# TouScruino-arm-ui2-v0.net
KiCad netlist of a schematic drawn in EAGLE
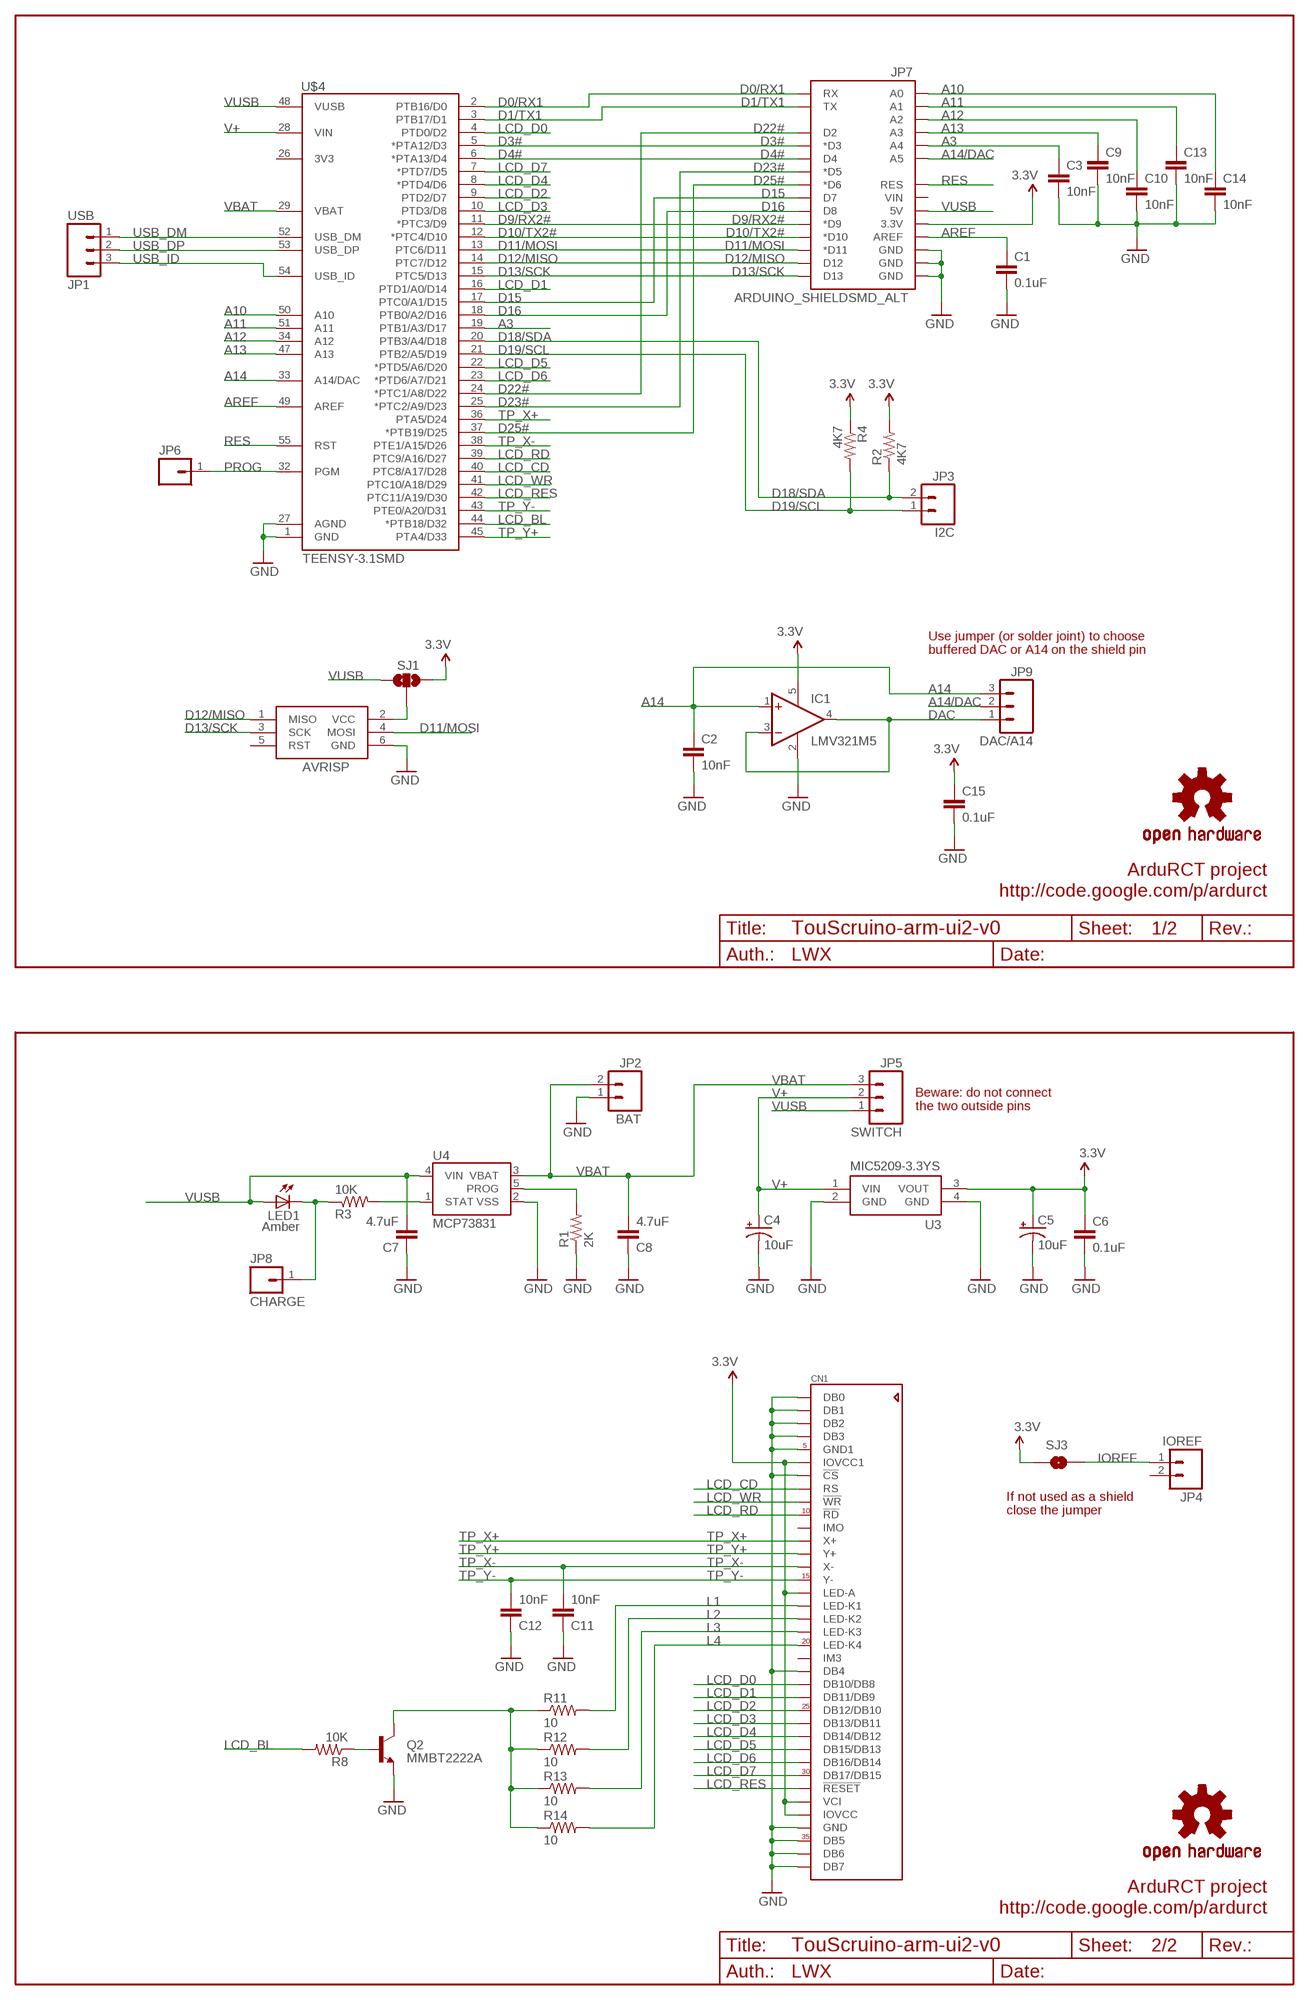
[diagram p0: schematic, sheet 1]

(export (version "E")
  (design (tool "Eeschema 10.0.6"))
  (components
    (comp (ref "AVRISP")
      (value "AVRISP")
      (footprint "eagle-import:2X3_SMD")
      (libsource (lib "eagle-import") (part "AVRISP"))
    )
    (comp (ref "C1")
      (value "0.1uF")
      (footprint "eagle-import:0805")
      (libsource (lib "eagle-import") (part "CAP0805"))
    )
    (comp (ref "C2")
      (value "10nF")
      (footprint "eagle-import:0805")
      (libsource (lib "eagle-import") (part "CAP0805"))
    )
    (comp (ref "C3")
      (value "10nF")
      (footprint "eagle-import:0805")
      (libsource (lib "eagle-import") (part "CAP0805"))
    )
    (comp (ref "C4")
      (value "10uF")
      (footprint "eagle-import:EIA3216")
      (libsource (lib "eagle-import") (part "CAP_POL1206"))
    )
    (comp (ref "C5")
      (value "10uF")
      (footprint "eagle-import:EIA3216")
      (libsource (lib "eagle-import") (part "CAP_POL1206"))
    )
    (comp (ref "C6")
      (value "0.1uF")
      (footprint "eagle-import:0805")
      (libsource (lib "eagle-import") (part "CAP0805"))
    )
    (comp (ref "C7")
      (value "4.7uF")
      (footprint "eagle-import:0805")
      (libsource (lib "eagle-import") (part "CAP0805"))
    )
    (comp (ref "C8")
      (value "4.7uF")
      (footprint "eagle-import:0805")
      (libsource (lib "eagle-import") (part "CAP0805"))
    )
    (comp (ref "C9")
      (value "10nF")
      (footprint "eagle-import:0805")
      (libsource (lib "eagle-import") (part "CAP0805"))
    )
    (comp (ref "C10")
      (value "10nF")
      (footprint "eagle-import:0805")
      (libsource (lib "eagle-import") (part "CAP0805"))
    )
    (comp (ref "C11")
      (value "10nF")
      (footprint "eagle-import:0805")
      (libsource (lib "eagle-import") (part "CAP0805"))
    )
    (comp (ref "C12")
      (value "10nF")
      (footprint "eagle-import:0805")
      (libsource (lib "eagle-import") (part "CAP0805"))
    )
    (comp (ref "C13")
      (value "10nF")
      (footprint "eagle-import:0805")
      (libsource (lib "eagle-import") (part "CAP0805"))
    )
    (comp (ref "C14")
      (value "10nF")
      (footprint "eagle-import:0805")
      (libsource (lib "eagle-import") (part "CAP0805"))
    )
    (comp (ref "C15")
      (value "0.1uF")
      (footprint "eagle-import:0805")
      (libsource (lib "eagle-import") (part "CAP0805"))
    )
    (comp (ref "CN1")
      (value "ILI9325_LCD1.0MM")
      (footprint "eagle-import:ILI9325_28INCH_TS")
      (libsource (lib "eagle-import") (part "ILI9325_LCD1.0MM"))
    )
    (comp (ref "IC1")
      (value "LMV321M5")
      (footprint "eagle-import:SOT23-5")
      (libsource (lib "eagle-import") (part "LMV321?M5"))
    )
    (comp (ref "JP1")
      (value "USB")
      (footprint "eagle-import:1X03_SMD_ALT")
      (libsource (lib "eagle-import") (part "M03SMD"))
    )
    (comp (ref "JP2")
      (value "BAT")
      (footprint "eagle-import:JST-2-SMD")
      (libsource (lib "eagle-import") (part "M02-JST-2MM-SMT"))
    )
    (comp (ref "JP3")
      (value "I2C")
      (footprint "eagle-import:1X02_SMD_ALT")
      (libsource (lib "eagle-import") (part "M02SMD_ALT"))
    )
    (comp (ref "JP4")
      (value "IOREF")
      (footprint "eagle-import:1X02_SMD_ALT")
      (libsource (lib "eagle-import") (part "M02SMD_ALT"))
    )
    (comp (ref "JP5")
      (value "SWITCH")
      (footprint "eagle-import:1X03_SMD_TH")
      (libsource (lib "eagle-import") (part "M03SMD_TH"))
    )
    (comp (ref "JP6")
      (value "M01SMD_TH")
      (footprint "eagle-import:1X01_SMD_TH")
      (libsource (lib "eagle-import") (part "M01SMD_TH"))
    )
    (comp (ref "JP7")
      (value "ARDUINO_SHIELDSMD_ALT")
      (footprint "eagle-import:ARDUINO_SHIELD_SMD_ALT")
      (libsource (lib "eagle-import") (part "ARDUINO_SHIELDSMD_ALT"))
    )
    (comp (ref "JP8")
      (value "CHARGE")
      (footprint "eagle-import:1X01_SMD")
      (libsource (lib "eagle-import") (part "M01SMD"))
    )
    (comp (ref "JP9")
      (value "DAC/A14")
      (footprint "eagle-import:1X03_SMD_SJ")
      (libsource (lib "eagle-import") (part "M03SMD_SJ"))
    )
    (comp (ref "LED1")
      (value "Amber")
      (footprint "eagle-import:LED")
      (libsource (lib "eagle-import") (part "LED"))
    )
    (comp (ref "Q2")
      (value "MMBT2222A")
      (footprint "eagle-import:SOT23-3")
      (libsource (lib "eagle-import") (part "TRANSISTOR_NPNSOT23-3"))
    )
    (comp (ref "R1")
      (value "2K")
      (footprint "eagle-import:0805")
      (libsource (lib "eagle-import") (part "RESISTOR0805-RES"))
    )
    (comp (ref "R2")
      (value "4K7")
      (footprint "eagle-import:0805")
      (libsource (lib "eagle-import") (part "RESISTOR0805-RES"))
    )
    (comp (ref "R3")
      (value "10K")
      (footprint "eagle-import:0805")
      (libsource (lib "eagle-import") (part "RESISTOR0805-RES"))
    )
    (comp (ref "R4")
      (value "4K7")
      (footprint "eagle-import:0805")
      (libsource (lib "eagle-import") (part "RESISTOR0805-RES"))
    )
    (comp (ref "R8")
      (value "10K")
      (footprint "eagle-import:0805")
      (libsource (lib "eagle-import") (part "RESISTOR0805-RES"))
    )
    (comp (ref "R11")
      (value "10")
      (footprint "eagle-import:0805")
      (libsource (lib "eagle-import") (part "RESISTOR0805-RES"))
    )
    (comp (ref "R12")
      (value "10")
      (footprint "eagle-import:0805")
      (libsource (lib "eagle-import") (part "RESISTOR0805-RES"))
    )
    (comp (ref "R13")
      (value "10")
      (footprint "eagle-import:0805")
      (libsource (lib "eagle-import") (part "RESISTOR0805-RES"))
    )
    (comp (ref "R14")
      (value "10")
      (footprint "eagle-import:0805")
      (libsource (lib "eagle-import") (part "RESISTOR0805-RES"))
    )
    (comp (ref "SJ1")
      (value "SJ_2WAYS")
      (footprint "eagle-import:SJ_2WAYS")
      (libsource (lib "eagle-import") (part "SJ_2WAYS"))
    )
    (comp (ref "SJ3")
      (value "SOLDERJUMPERNO")
      (footprint "eagle-import:SJ_2S-NO")
      (libsource (lib "eagle-import") (part "SOLDERJUMPERNO"))
    )
    (comp (ref "U$3")
      (value "OSHW-LOGOM")
      (footprint "eagle-import:OSHW-LOGO-M")
      (libsource (lib "eagle-import") (part "OSHW-LOGOM"))
    )
    (comp (ref "U$4")
      (value "TEENSY-3.1SMD")
      (footprint "eagle-import:TEENSY-3.1_HSMD")
      (libsource (lib "eagle-import") (part "TEENSY-3.1SMD"))
    )
    (comp (ref "U$5")
      (value "OSHW-LOGOM")
      (footprint "eagle-import:OSHW-LOGO-M")
      (libsource (lib "eagle-import") (part "OSHW-LOGOM"))
    )
    (comp (ref "U3")
      (value "MIC5209-3.3YS")
      (footprint "eagle-import:SOT223")
      (libsource (lib "eagle-import") (part "MIC5209"))
    )
    (comp (ref "U4")
      (value "MCP73831")
      (footprint "eagle-import:SOT23-5")
      (libsource (lib "eagle-import") (part "MCP73831"))
    )
  )
  (nets
    (net (code "1") (name "/A3") (class "Default")
      (node (ref "C3") (pin "1") (pinfunction "1_1") (pintype "passive"))
      (node (ref "JP7") (pin "A4") (pinfunction "A4_A4") (pintype "bidirectional"))
      (node (ref "U$4") (pin "19") (pinfunction "PTB1/A3/D17_19") (pintype "bidirectional"))
    )
    (net (code "2") (name "/A10") (class "Default")
      (node (ref "C14") (pin "1") (pinfunction "1_1") (pintype "passive"))
      (node (ref "JP7") (pin "A0") (pinfunction "A0_A0") (pintype "bidirectional"))
      (node (ref "U$4") (pin "50") (pinfunction "A10_50") (pintype "bidirectional"))
    )
    (net (code "3") (name "/A11") (class "Default")
      (node (ref "C13") (pin "1") (pinfunction "1_1") (pintype "passive"))
      (node (ref "JP7") (pin "A1") (pinfunction "A1_A1") (pintype "bidirectional"))
      (node (ref "U$4") (pin "51") (pinfunction "A11_51") (pintype "bidirectional"))
    )
    (net (code "4") (name "/A12") (class "Default")
      (node (ref "C10") (pin "1") (pinfunction "1_1") (pintype "passive"))
      (node (ref "JP7") (pin "A2") (pinfunction "A2_A2") (pintype "bidirectional"))
      (node (ref "U$4") (pin "34") (pinfunction "A12_34") (pintype "bidirectional"))
    )
    (net (code "5") (name "/A13") (class "Default")
      (node (ref "C9") (pin "1") (pinfunction "1_1") (pintype "passive"))
      (node (ref "JP7") (pin "A3") (pinfunction "A3_A3") (pintype "bidirectional"))
      (node (ref "U$4") (pin "47") (pinfunction "A13_47") (pintype "bidirectional"))
    )
    (net (code "6") (name "/A14") (class "Default")
      (node (ref "C2") (pin "1") (pinfunction "1_1") (pintype "passive"))
      (node (ref "IC1") (pin "1") (pinfunction "+IN_1") (pintype "input"))
      (node (ref "JP9") (pin "3") (pinfunction "3_3") (pintype "passive"))
      (node (ref "U$4") (pin "33") (pinfunction "A14/DAC_33") (pintype "bidirectional"))
    )
    (net (code "7") (name "/A14{slash}DAC") (class "Default")
      (node (ref "JP7") (pin "A5") (pinfunction "A5_A5") (pintype "bidirectional"))
      (node (ref "JP9") (pin "2") (pinfunction "2_2") (pintype "passive"))
    )
    (net (code "8") (name "/AREF") (class "Default")
      (node (ref "C1") (pin "1") (pinfunction "1_1") (pintype "passive"))
      (node (ref "JP7") (pin "AREF") (pinfunction "AREF_AREF") (pintype "bidirectional"))
      (node (ref "U$4") (pin "49") (pinfunction "AREF_49") (pintype "bidirectional"))
    )
    (net (code "9") (name "/D0{slash}RX1") (class "Default")
      (node (ref "JP7") (pin "RX") (pinfunction "RX_RX") (pintype "bidirectional"))
      (node (ref "U$4") (pin "2") (pinfunction "PTB16/D0_2") (pintype "bidirectional"))
    )
    (net (code "10") (name "/D1{slash}TX1") (class "Default")
      (node (ref "JP7") (pin "TX") (pinfunction "TX_TX") (pintype "bidirectional"))
      (node (ref "U$4") (pin "3") (pinfunction "PTB17/D1_3") (pintype "bidirectional"))
    )
    (net (code "11") (name "/D3#") (class "Default")
      (node (ref "JP7") (pin "D3") (pinfunction "*D3_D3") (pintype "bidirectional"))
      (node (ref "U$4") (pin "5") (pinfunction "*PTA12/D3_5") (pintype "bidirectional"))
    )
    (net (code "12") (name "/D4#") (class "Default")
      (node (ref "JP7") (pin "D4") (pinfunction "D4_D4") (pintype "bidirectional"))
      (node (ref "U$4") (pin "6") (pinfunction "*PTA13/D4_6") (pintype "bidirectional"))
    )
    (net (code "13") (name "/D9{slash}RX2#") (class "Default")
      (node (ref "JP7") (pin "D9") (pinfunction "*D9_D9") (pintype "bidirectional"))
      (node (ref "U$4") (pin "11") (pinfunction "*PTC3/D9_11") (pintype "bidirectional"))
    )
    (net (code "14") (name "/D10{slash}TX2#") (class "Default")
      (node (ref "JP7") (pin "D10") (pinfunction "*D10_D10") (pintype "bidirectional"))
      (node (ref "U$4") (pin "12") (pinfunction "*PTC4/D10_12") (pintype "bidirectional"))
    )
    (net (code "15") (name "/D11{slash}MOSI") (class "Default")
      (node (ref "AVRISP") (pin "4") (pinfunction "MOSI_4") (pintype "output"))
      (node (ref "JP7") (pin "D11") (pinfunction "*D11_D11") (pintype "bidirectional"))
      (node (ref "U$4") (pin "13") (pinfunction "PTC6/D11_13") (pintype "bidirectional"))
    )
    (net (code "16") (name "/D12{slash}MISO") (class "Default")
      (node (ref "AVRISP") (pin "1") (pinfunction "MISO_1") (pintype "input"))
      (node (ref "JP7") (pin "D12") (pinfunction "D12_D12") (pintype "bidirectional"))
      (node (ref "U$4") (pin "14") (pinfunction "PTC7/D12_14") (pintype "bidirectional"))
    )
    (net (code "17") (name "/D13{slash}SCK") (class "Default")
      (node (ref "AVRISP") (pin "3") (pinfunction "SCK_3") (pintype "output"))
      (node (ref "JP7") (pin "D13") (pinfunction "D13_D13") (pintype "bidirectional"))
      (node (ref "U$4") (pin "15") (pinfunction "PTC5/D13_15") (pintype "bidirectional"))
    )
    (net (code "18") (name "/D15") (class "Default")
      (node (ref "JP7") (pin "D7") (pinfunction "D7_D7") (pintype "bidirectional"))
      (node (ref "U$4") (pin "17") (pinfunction "PTC0/A1/D15_17") (pintype "bidirectional"))
    )
    (net (code "19") (name "/D16") (class "Default")
      (node (ref "JP7") (pin "D8") (pinfunction "D8_D8") (pintype "bidirectional"))
      (node (ref "U$4") (pin "18") (pinfunction "PTB0/A2/D16_18") (pintype "bidirectional"))
    )
    (net (code "20") (name "/D18{slash}SDA") (class "Default")
      (node (ref "JP3") (pin "2") (pinfunction "2_2") (pintype "passive"))
      (node (ref "R2") (pin "1") (pinfunction "1_1") (pintype "passive"))
      (node (ref "U$4") (pin "20") (pinfunction "PTB3/A4/D18_20") (pintype "bidirectional"))
    )
    (net (code "21") (name "/D19{slash}SCL") (class "Default")
      (node (ref "JP3") (pin "1") (pinfunction "1_1") (pintype "passive"))
      (node (ref "R4") (pin "2") (pinfunction "2_2") (pintype "passive"))
      (node (ref "U$4") (pin "21") (pinfunction "PTB2/A5/D19_21") (pintype "bidirectional"))
    )
    (net (code "22") (name "/D22#") (class "Default")
      (node (ref "JP7") (pin "D2") (pinfunction "D2_D2") (pintype "bidirectional"))
      (node (ref "U$4") (pin "24") (pinfunction "*PTC1/A8/D22_24") (pintype "bidirectional"))
    )
    (net (code "23") (name "/D23#") (class "Default")
      (node (ref "JP7") (pin "D5") (pinfunction "*D5_D5") (pintype "bidirectional"))
      (node (ref "U$4") (pin "25") (pinfunction "*PTC2/A9/D23_25") (pintype "bidirectional"))
    )
    (net (code "24") (name "/D25#") (class "Default")
      (node (ref "JP7") (pin "D6") (pinfunction "*D6_D6") (pintype "bidirectional"))
      (node (ref "U$4") (pin "37") (pinfunction "*PTB19/D25_37") (pintype "bidirectional"))
    )
    (net (code "25") (name "/DAC") (class "Default")
      (node (ref "IC1") (pin "3") (pinfunction "-IN_3") (pintype "input"))
      (node (ref "IC1") (pin "4") (pinfunction "OUT_4") (pintype "output"))
      (node (ref "JP9") (pin "1") (pinfunction "1_1") (pintype "passive"))
    )
    (net (code "26") (name "/IOREF") (class "Default")
      (node (ref "JP4") (pin "1") (pinfunction "1_1") (pintype "passive"))
      (node (ref "SJ3") (pin "2") (pinfunction "2_2") (pintype "passive"))
    )
    (net (code "27") (name "/L1") (class "Default")
      (node (ref "CN1") (pin "17") (pinfunction "LED-K1_17") (pintype "passive"))
      (node (ref "R11") (pin "2") (pinfunction "2_2") (pintype "passive"))
    )
    (net (code "28") (name "/L2") (class "Default")
      (node (ref "CN1") (pin "18") (pinfunction "LED-K2_18") (pintype "passive"))
      (node (ref "R12") (pin "2") (pinfunction "2_2") (pintype "passive"))
    )
    (net (code "29") (name "/L3") (class "Default")
      (node (ref "CN1") (pin "19") (pinfunction "LED-K3_19") (pintype "passive"))
      (node (ref "R13") (pin "2") (pinfunction "2_2") (pintype "passive"))
    )
    (net (code "30") (name "/L4") (class "Default")
      (node (ref "CN1") (pin "20") (pinfunction "LED-K4_20") (pintype "passive"))
      (node (ref "R14") (pin "2") (pinfunction "2_2") (pintype "passive"))
    )
    (net (code "31") (name "/LCD_BL") (class "Default")
      (node (ref "R8") (pin "2") (pinfunction "2_2") (pintype "passive"))
      (node (ref "U$4") (pin "44") (pinfunction "*PTB18/D32_44") (pintype "bidirectional"))
    )
    (net (code "32") (name "/LCD_CD") (class "Default")
      (node (ref "CN1") (pin "8") (pinfunction "RS_8") (pintype "passive"))
      (node (ref "U$4") (pin "40") (pinfunction "PTC8/A17/D28_40") (pintype "bidirectional"))
    )
    (net (code "33") (name "/LCD_D0") (class "Default")
      (node (ref "CN1") (pin "23") (pinfunction "DB10/DB8_23") (pintype "passive"))
      (node (ref "U$4") (pin "4") (pinfunction "PTD0/D2_4") (pintype "bidirectional"))
    )
    (net (code "34") (name "/LCD_D1") (class "Default")
      (node (ref "CN1") (pin "24") (pinfunction "DB11/DB9_24") (pintype "passive"))
      (node (ref "U$4") (pin "16") (pinfunction "PTD1/A0/D14_16") (pintype "bidirectional"))
    )
    (net (code "35") (name "/LCD_D2") (class "Default")
      (node (ref "CN1") (pin "25") (pinfunction "DB12/DB10_25") (pintype "passive"))
      (node (ref "U$4") (pin "9") (pinfunction "PTD2/D7_9") (pintype "bidirectional"))
    )
    (net (code "36") (name "/LCD_D3") (class "Default")
      (node (ref "CN1") (pin "26") (pinfunction "DB13/DB11_26") (pintype "passive"))
      (node (ref "U$4") (pin "10") (pinfunction "PTD3/D8_10") (pintype "bidirectional"))
    )
    (net (code "37") (name "/LCD_D4") (class "Default")
      (node (ref "CN1") (pin "27") (pinfunction "DB14/DB12_27") (pintype "passive"))
      (node (ref "U$4") (pin "8") (pinfunction "*PTD4/D6_8") (pintype "bidirectional"))
    )
    (net (code "38") (name "/LCD_D5") (class "Default")
      (node (ref "CN1") (pin "28") (pinfunction "DB15/DB13_28") (pintype "passive"))
      (node (ref "U$4") (pin "22") (pinfunction "*PTD5/A6/D20_22") (pintype "bidirectional"))
    )
    (net (code "39") (name "/LCD_D6") (class "Default")
      (node (ref "CN1") (pin "29") (pinfunction "DB16/DB14_29") (pintype "passive"))
      (node (ref "U$4") (pin "23") (pinfunction "*PTD6/A7/D21_23") (pintype "bidirectional"))
    )
    (net (code "40") (name "/LCD_D7") (class "Default")
      (node (ref "CN1") (pin "30") (pinfunction "DB17/DB15_30") (pintype "passive"))
      (node (ref "U$4") (pin "7") (pinfunction "*PTD7/D5_7") (pintype "bidirectional"))
    )
    (net (code "41") (name "/LCD_RD") (class "Default")
      (node (ref "CN1") (pin "10") (pinfunction "~{RD}_10") (pintype "passive"))
      (node (ref "U$4") (pin "39") (pinfunction "PTC9/A16/D27_39") (pintype "bidirectional"))
    )
    (net (code "42") (name "/LCD_RES") (class "Default")
      (node (ref "CN1") (pin "31") (pinfunction "~{RESET}_31") (pintype "passive"))
      (node (ref "U$4") (pin "42") (pinfunction "PTC11/A19/D30_42") (pintype "bidirectional"))
    )
    (net (code "43") (name "/LCD_WR") (class "Default")
      (node (ref "CN1") (pin "9") (pinfunction "~{WR}_9") (pintype "passive"))
      (node (ref "U$4") (pin "41") (pinfunction "PTC10/A18/D29_41") (pintype "bidirectional"))
    )
    (net (code "44") (name "/PROG") (class "Default")
      (node (ref "JP6") (pin "1") (pinfunction "1_1") (pintype "passive"))
      (node (ref "U$4") (pin "32") (pinfunction "PGM_32") (pintype "bidirectional"))
    )
    (net (code "45") (name "/RES") (class "Default")
      (node (ref "JP7") (pin "RES") (pinfunction "RES_RES") (pintype "bidirectional"))
      (node (ref "U$4") (pin "55") (pinfunction "RST_55") (pintype "bidirectional"))
    )
    (net (code "46") (name "/TP_X+") (class "Default")
      (node (ref "CN1") (pin "12") (pinfunction "X+_12") (pintype "passive"))
      (node (ref "U$4") (pin "36") (pinfunction "PTA5/D24_36") (pintype "bidirectional"))
    )
    (net (code "47") (name "/TP_X-") (class "Default")
      (node (ref "C11") (pin "2") (pinfunction "2_2") (pintype "passive"))
      (node (ref "CN1") (pin "14") (pinfunction "X-_14") (pintype "passive"))
      (node (ref "U$4") (pin "38") (pinfunction "PTE1/A15/D26_38") (pintype "bidirectional"))
    )
    (net (code "48") (name "/TP_Y+") (class "Default")
      (node (ref "CN1") (pin "13") (pinfunction "Y+_13") (pintype "passive"))
      (node (ref "U$4") (pin "45") (pinfunction "PTA4/D33_45") (pintype "bidirectional"))
    )
    (net (code "49") (name "/TP_Y-") (class "Default")
      (node (ref "C12") (pin "2") (pinfunction "2_2") (pintype "passive"))
      (node (ref "CN1") (pin "15") (pinfunction "Y-_15") (pintype "passive"))
      (node (ref "U$4") (pin "43") (pinfunction "PTE0/A20/D31_43") (pintype "bidirectional"))
    )
    (net (code "50") (name "/USB_DM") (class "Default")
      (node (ref "JP1") (pin "1") (pinfunction "1_1") (pintype "passive"))
      (node (ref "U$4") (pin "52") (pinfunction "USB_DM_52") (pintype "bidirectional"))
    )
    (net (code "51") (name "/USB_DP") (class "Default")
      (node (ref "JP1") (pin "2") (pinfunction "2_2") (pintype "passive"))
      (node (ref "U$4") (pin "53") (pinfunction "USB_DP_53") (pintype "bidirectional"))
    )
    (net (code "52") (name "/USB_ID") (class "Default")
      (node (ref "JP1") (pin "3") (pinfunction "3_3") (pintype "passive"))
      (node (ref "U$4") (pin "54") (pinfunction "USB_ID_54") (pintype "bidirectional"))
    )
    (net (code "53") (name "/V+") (class "Default")
      (node (ref "C4") (pin "A") (pinfunction "+_A") (pintype "passive"))
      (node (ref "JP5") (pin "2") (pinfunction "2_2") (pintype "passive"))
      (node (ref "U$4") (pin "28") (pinfunction "VIN_28") (pintype "bidirectional"))
      (node (ref "U3") (pin "1") (pinfunction "VIN_1") (pintype "bidirectional"))
    )
    (net (code "54") (name "/VBAT") (class "Default")
      (node (ref "C8") (pin "2") (pinfunction "2_2") (pintype "passive"))
      (node (ref "JP2") (pin "2") (pinfunction "2_2") (pintype "passive"))
      (node (ref "JP5") (pin "3") (pinfunction "3_3") (pintype "passive"))
      (node (ref "U$4") (pin "29") (pinfunction "VBAT_29") (pintype "bidirectional"))
      (node (ref "U4") (pin "3") (pinfunction "VBAT_3") (pintype "power_in"))
    )
    (net (code "55") (name "/VUSB") (class "Default")
      (node (ref "C7") (pin "2") (pinfunction "2_2") (pintype "passive"))
      (node (ref "JP5") (pin "1") (pinfunction "1_1") (pintype "passive"))
      (node (ref "JP7") (pin "5V") (pinfunction "5V_5V") (pintype "bidirectional"))
      (node (ref "LED1") (pin "A1") (pinfunction "A_A1") (pintype "passive"))
      (node (ref "SJ1") (pin "1") (pinfunction "1_1") (pintype "passive"))
      (node (ref "U$4") (pin "48") (pinfunction "VUSB_48") (pintype "bidirectional"))
      (node (ref "U4") (pin "4") (pinfunction "VIN_4") (pintype "power_in"))
    )
    (net (code "56") (name "3.3V") (class "Default")
      (node (ref "C15") (pin "1") (pinfunction "1_1") (pintype "passive"))
      (node (ref "C5") (pin "A") (pinfunction "+_A") (pintype "passive"))
      (node (ref "C6") (pin "1") (pinfunction "1_1") (pintype "passive"))
      (node (ref "CN1") (pin "16") (pinfunction "LED-A_16") (pintype "passive"))
      (node (ref "CN1") (pin "32") (pinfunction "VCI_32") (pintype "power_in"))
      (node (ref "CN1") (pin "33") (pinfunction "IOVCC_33") (pintype "power_in"))
      (node (ref "CN1") (pin "6") (pinfunction "IOVCC1_6") (pintype "power_in"))
      (node (ref "IC1") (pin "5") (pinfunction "V+_5") (pintype "power_in"))
      (node (ref "JP7") (pin "3.3V") (pinfunction "3.3V_3.3V") (pintype "bidirectional"))
      (node (ref "R2") (pin "2") (pinfunction "2_2") (pintype "passive"))
      (node (ref "R4") (pin "1") (pinfunction "1_1") (pintype "passive"))
      (node (ref "SJ1") (pin "3") (pinfunction "3_3") (pintype "passive"))
      (node (ref "SJ3") (pin "1") (pinfunction "1_1") (pintype "passive"))
      (node (ref "U3") (pin "3") (pinfunction "VOUT_3") (pintype "bidirectional"))
    )
    (net (code "57") (name "GND") (class "Default")
      (node (ref "AVRISP") (pin "6") (pinfunction "GND_6") (pintype "power_in"))
      (node (ref "C1") (pin "2") (pinfunction "2_2") (pintype "passive"))
      (node (ref "C10") (pin "2") (pinfunction "2_2") (pintype "passive"))
      (node (ref "C11") (pin "1") (pinfunction "1_1") (pintype "passive"))
      (node (ref "C12") (pin "1") (pinfunction "1_1") (pintype "passive"))
      (node (ref "C13") (pin "2") (pinfunction "2_2") (pintype "passive"))
      (node (ref "C14") (pin "2") (pinfunction "2_2") (pintype "passive"))
      (node (ref "C15") (pin "2") (pinfunction "2_2") (pintype "passive"))
      (node (ref "C2") (pin "2") (pinfunction "2_2") (pintype "passive"))
      (node (ref "C3") (pin "2") (pinfunction "2_2") (pintype "passive"))
      (node (ref "C4") (pin "C") (pinfunction "-_C") (pintype "passive"))
      (node (ref "C5") (pin "C") (pinfunction "-_C") (pintype "passive"))
      (node (ref "C6") (pin "2") (pinfunction "2_2") (pintype "passive"))
      (node (ref "C7") (pin "1") (pinfunction "1_1") (pintype "passive"))
      (node (ref "C8") (pin "1") (pinfunction "1_1") (pintype "passive"))
      (node (ref "C9") (pin "2") (pinfunction "2_2") (pintype "passive"))
      (node (ref "CN1") (pin "1") (pinfunction "DB0_1") (pintype "passive"))
      (node (ref "CN1") (pin "2") (pinfunction "DB1_2") (pintype "passive"))
      (node (ref "CN1") (pin "22") (pinfunction "DB4_22") (pintype "passive"))
      (node (ref "CN1") (pin "3") (pinfunction "DB2_3") (pintype "passive"))
      (node (ref "CN1") (pin "34") (pinfunction "GND_34") (pintype "power_in"))
      (node (ref "CN1") (pin "35") (pinfunction "DB5_35") (pintype "passive"))
      (node (ref "CN1") (pin "36") (pinfunction "DB6_36") (pintype "passive"))
      (node (ref "CN1") (pin "37") (pinfunction "DB7_37") (pintype "passive"))
      (node (ref "CN1") (pin "4") (pinfunction "DB3_4") (pintype "passive"))
      (node (ref "CN1") (pin "5") (pinfunction "GND1_5") (pintype "power_in"))
      (node (ref "CN1") (pin "7") (pinfunction "~{CS}_7") (pintype "passive"))
      (node (ref "IC1") (pin "2") (pinfunction "V-_2") (pintype "power_in"))
      (node (ref "JP2") (pin "1") (pinfunction "1_1") (pintype "passive"))
      (node (ref "JP7") (pin "GND@0") (pinfunction "GND_GND@0") (pintype "bidirectional"))
      (node (ref "JP7") (pin "GND@1") (pinfunction "GND_GND@1") (pintype "bidirectional"))
      (node (ref "JP7") (pin "GND@2") (pinfunction "GND_GND@2") (pintype "bidirectional"))
      (node (ref "Q2") (pin "2") (pinfunction "E_2") (pintype "passive"))
      (node (ref "R1") (pin "1") (pinfunction "1_1") (pintype "passive"))
      (node (ref "U$4") (pin "1") (pinfunction "GND_1") (pintype "bidirectional"))
      (node (ref "U$4") (pin "27") (pinfunction "AGND_27") (pintype "bidirectional"))
      (node (ref "U3") (pin "2") (pinfunction "GND_2") (pintype "bidirectional"))
      (node (ref "U3") (pin "4") (pinfunction "GND_4") (pintype "bidirectional"))
      (node (ref "U4") (pin "2") (pinfunction "VSS_2") (pintype "power_in"))
    )
    (net (code "58") (name "Net-(AVRISP-VCC)") (class "Default")
      (node (ref "AVRISP") (pin "2") (pinfunction "VCC_2") (pintype "power_in"))
      (node (ref "SJ1") (pin "2") (pinfunction "2_2") (pintype "passive"))
    )
    (net (code "59") (name "Net-(LED1-C)") (class "Default")
      (node (ref "JP8") (pin "1") (pinfunction "1_1") (pintype "passive"))
      (node (ref "LED1") (pin "C1") (pinfunction "C_C1") (pintype "passive"))
      (node (ref "R3") (pin "1") (pinfunction "1_1") (pintype "passive"))
    )
    (net (code "60") (name "Net-(Q2-B)") (class "Default")
      (node (ref "Q2") (pin "1") (pinfunction "B_1") (pintype "passive"))
      (node (ref "R8") (pin "1") (pinfunction "1_1") (pintype "passive"))
    )
    (net (code "61") (name "Net-(Q2-C)") (class "Default")
      (node (ref "Q2") (pin "3") (pinfunction "C_3") (pintype "passive"))
      (node (ref "R11") (pin "1") (pinfunction "1_1") (pintype "passive"))
      (node (ref "R12") (pin "1") (pinfunction "1_1") (pintype "passive"))
      (node (ref "R13") (pin "1") (pinfunction "1_1") (pintype "passive"))
      (node (ref "R14") (pin "1") (pinfunction "1_1") (pintype "passive"))
    )
    (net (code "62") (name "Net-(U4-PROG)") (class "Default")
      (node (ref "R1") (pin "2") (pinfunction "2_2") (pintype "passive"))
      (node (ref "U4") (pin "5") (pinfunction "PROG_5") (pintype "input"))
    )
    (net (code "63") (name "Net-(U4-STAT)") (class "Default")
      (node (ref "R3") (pin "2") (pinfunction "2_2") (pintype "passive"))
      (node (ref "U4") (pin "1") (pinfunction "STAT_1") (pintype "output"))
    )
    (net (code "64") (name "unconnected-(AVRISP-RST-Pad5)") (class "Default")
      (node (ref "AVRISP") (pin "5") (pinfunction "RST_5") (pintype "output"))
    )
    (net (code "65") (name "unconnected-(CN1-IM3-Pad21)") (class "Default")
      (node (ref "CN1") (pin "21") (pinfunction "IM3_21") (pintype "passive"))
    )
    (net (code "66") (name "unconnected-(CN1-IMO-Pad11)") (class "Default")
      (node (ref "CN1") (pin "11") (pinfunction "IMO_11") (pintype "passive"))
    )
    (net (code "67") (name "unconnected-(JP4-Pad2)") (class "Default")
      (node (ref "JP4") (pin "2") (pinfunction "2_2") (pintype "passive"))
    )
    (net (code "68") (name "unconnected-(JP7-PadVIN)") (class "Default")
      (node (ref "JP7") (pin "VIN") (pinfunction "VIN_VIN") (pintype "bidirectional"))
    )
    (net (code "69") (name "unconnected-(U$4-3V3-Pad26)") (class "Default")
      (node (ref "U$4") (pin "26") (pinfunction "3V3_26") (pintype "bidirectional"))
    )
  )
)
